# FPGA2.net
KiCad netlist of a schematic drawn in Altium Designer
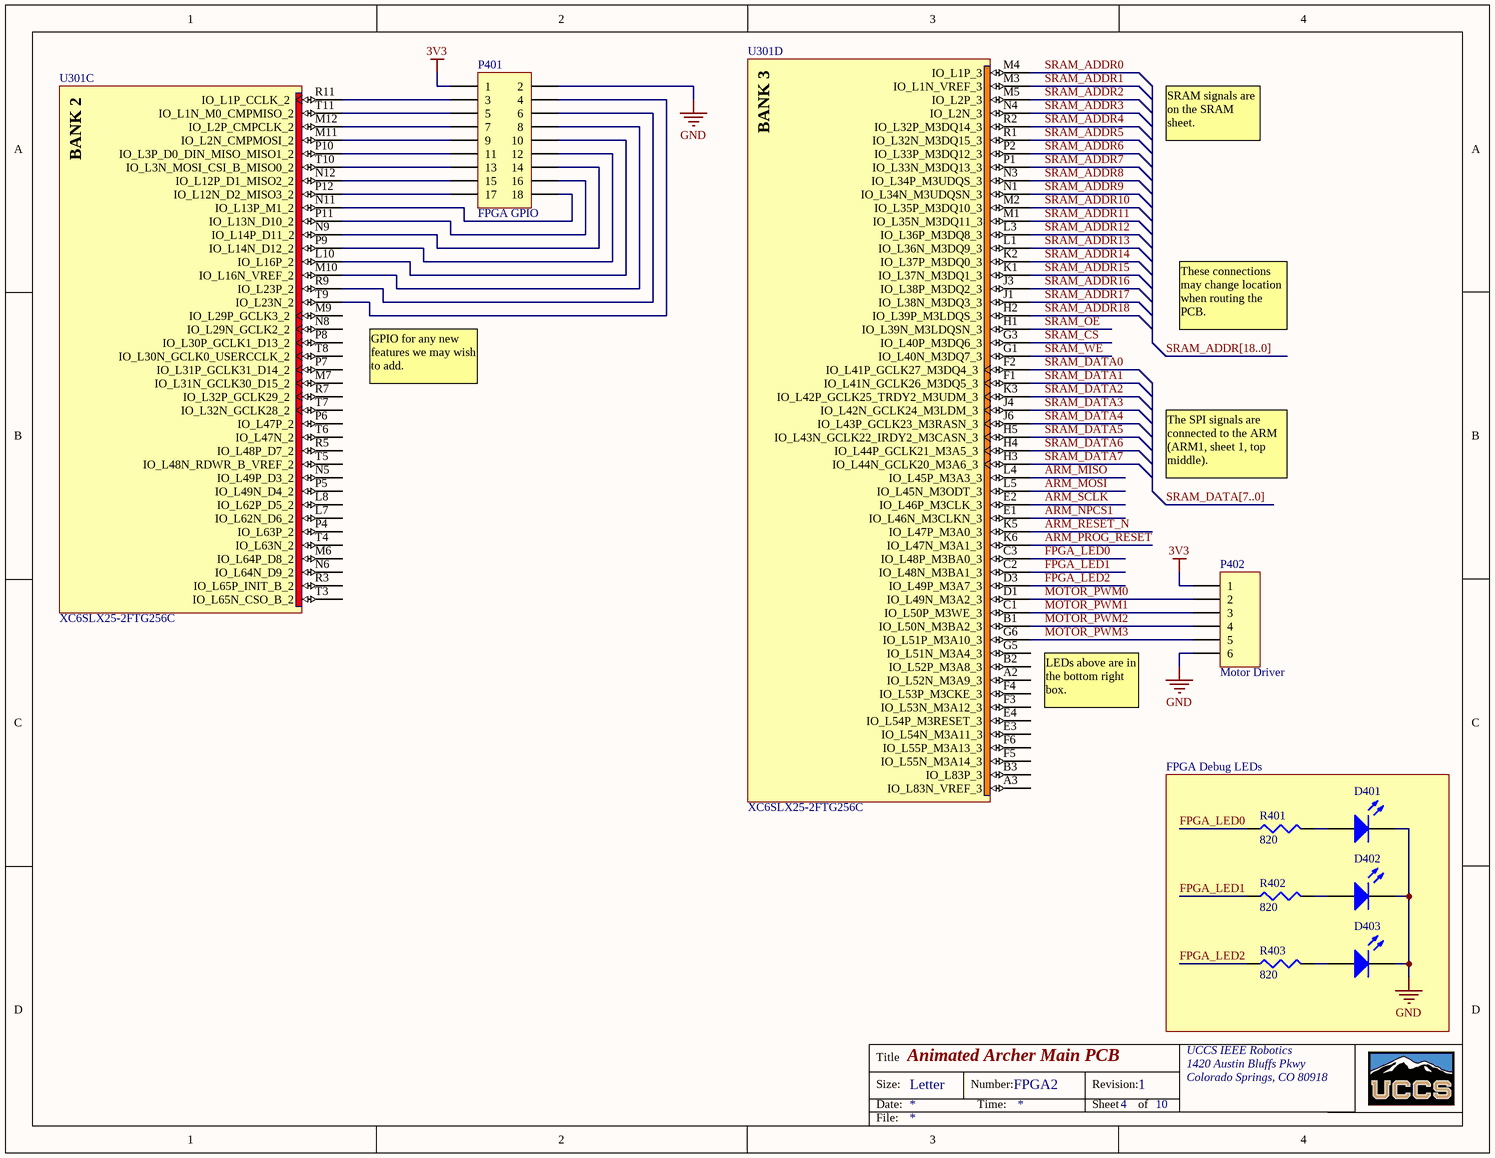
[diagram p0: FPGA2.SchDoc]

(export (version "E")
  (design (tool "Eeschema 10.0.6"))
  (components
    (comp (ref "D401")
      (value "Green")
      (footprint "1608[0603]")
      (description "Typical RED, GREEN, YELLOW, AMBER GaAs LED")
      (fields (field (name "PUBLISHER") "Altium Limited"))
      (libsource (lib "Miscellaneous Devices") (part "LED2"))
    )
    (comp (ref "D402")
      (value "Green")
      (footprint "1608[0603]")
      (description "Typical RED, GREEN, YELLOW, AMBER GaAs LED")
      (fields (field (name "PUBLISHER") "Altium Limited"))
      (libsource (lib "Miscellaneous Devices") (part "LED2"))
    )
    (comp (ref "D403")
      (value "Green")
      (footprint "1608[0603]")
      (description "Typical RED, GREEN, YELLOW, AMBER GaAs LED")
      (fields (field (name "PUBLISHER") "Altium Limited"))
      (libsource (lib "Miscellaneous Devices") (part "LED2"))
    )
    (comp (ref "P401")
      (value "FPGA GPIO")
      (footprint "HDR2X9")
      (description "Header, 9-Pin, Dual row")
      (fields (field (name "PUBLISHER") "Altium Limited"))
      (libsource (lib "Miscellaneous Connectors") (part "Header 9X2"))
    )
    (comp (ref "P402")
      (value "Motor Driver")
      (footprint "HDR1X6")
      (description "Header, 6-Pin")
      (fields (field (name "PUBLISHER") "Altium Limited"))
      (libsource (lib "Miscellaneous Connectors") (part "Header 6"))
    )
    (comp (ref "R401")
      (value "820")
      (footprint "J1-0603")
      (description "Resistor")
      (fields (field (name "Comment") "Res3") (field (name "PUBLISHER") "Altium Limited"))
      (libsource (lib "Miscellaneous Devices") (part "Res3"))
    )
    (comp (ref "R402")
      (value "820")
      (footprint "J1-0603")
      (description "Resistor")
      (fields (field (name "Comment") "Res3") (field (name "PUBLISHER") "Altium Limited"))
      (libsource (lib "Miscellaneous Devices") (part "Res3"))
    )
    (comp (ref "R403")
      (value "820")
      (footprint "J1-0603")
      (description "Resistor")
      (fields (field (name "Comment") "Res3") (field (name "PUBLISHER") "Altium Limited"))
      (libsource (lib "Miscellaneous Devices") (part "Res3"))
    )
    (comp (ref "U301")
      (value "XC6SLX25-2FTG256C")
      (footprint "FTG256")
      (fields (field (name "PUBLISHER") "Altium Limited"))
      (libsource (lib "Animated Archer") (part "XC6SLX25-2FTG256C"))
    )
  )
  (nets
    (net (code "1") (name "/ARM_MISO") (class "Default")
      (node (ref "U301") (pin "L4") (pinfunction "IO_L45P_M3A3_3_L4") (pintype "bidirectional"))
    )
    (net (code "2") (name "/ARM_MOSI") (class "Default")
      (node (ref "U301") (pin "L5") (pinfunction "IO_L45N_M3ODT_3_L5") (pintype "bidirectional"))
    )
    (net (code "3") (name "/ARM_NPCS1") (class "Default")
      (node (ref "U301") (pin "E1") (pinfunction "IO_L46N_M3CLKN_3_E1") (pintype "bidirectional"))
    )
    (net (code "4") (name "/ARM_PROG_RESET") (class "Default")
      (node (ref "U301") (pin "K6") (pinfunction "IO_L47N_M3A1_3_K6") (pintype "bidirectional"))
    )
    (net (code "5") (name "/ARM_RESET_N") (class "Default")
      (node (ref "U301") (pin "K5") (pinfunction "IO_L47P_M3A0_3_K5") (pintype "bidirectional"))
    )
    (net (code "6") (name "/ARM_SCLK") (class "Default")
      (node (ref "U301") (pin "E2") (pinfunction "IO_L46P_M3CLK_3_E2") (pintype "bidirectional"))
    )
    (net (code "7") (name "/FPGA_LED0") (class "Default")
      (node (ref "R401") (pin "1") (pinfunction "1_1") (pintype "passive"))
      (node (ref "U301") (pin "C3") (pinfunction "IO_L48P_M3BA0_3_C3") (pintype "bidirectional"))
    )
    (net (code "8") (name "/FPGA_LED1") (class "Default")
      (node (ref "R402") (pin "1") (pinfunction "1_1") (pintype "passive"))
      (node (ref "U301") (pin "C2") (pinfunction "IO_L48N_M3BA1_3_C2") (pintype "bidirectional"))
    )
    (net (code "9") (name "/FPGA_LED2") (class "Default")
      (node (ref "R403") (pin "1") (pinfunction "1_1") (pintype "passive"))
      (node (ref "U301") (pin "D3") (pinfunction "IO_L49P_M3A7_3_D3") (pintype "bidirectional"))
    )
    (net (code "10") (name "/MOTOR_PWM0") (class "Default")
      (node (ref "P402") (pin "2") (pinfunction "2_2") (pintype "passive"))
      (node (ref "U301") (pin "D1") (pinfunction "IO_L49N_M3A2_3_D1") (pintype "bidirectional"))
    )
    (net (code "11") (name "/MOTOR_PWM1") (class "Default")
      (node (ref "P402") (pin "3") (pinfunction "3_3") (pintype "passive"))
      (node (ref "U301") (pin "C1") (pinfunction "IO_L50P_M3WE_3_C1") (pintype "bidirectional"))
    )
    (net (code "12") (name "/MOTOR_PWM2") (class "Default")
      (node (ref "P402") (pin "4") (pinfunction "4_4") (pintype "passive"))
      (node (ref "U301") (pin "B1") (pinfunction "IO_L50N_M3BA2_3_B1") (pintype "bidirectional"))
    )
    (net (code "13") (name "/MOTOR_PWM3") (class "Default")
      (node (ref "P402") (pin "5") (pinfunction "5_5") (pintype "passive"))
      (node (ref "U301") (pin "G6") (pinfunction "IO_L51P_M3A10_3_G6") (pintype "bidirectional"))
    )
    (net (code "14") (name "/SRAM_ADDR0") (class "Default")
      (node (ref "U301") (pin "M4") (pinfunction "IO_L1P_3_M4") (pintype "bidirectional"))
    )
    (net (code "15") (name "/SRAM_ADDR1") (class "Default")
      (node (ref "U301") (pin "M3") (pinfunction "IO_L1N_VREF_3_M3") (pintype "bidirectional"))
    )
    (net (code "16") (name "/SRAM_ADDR2") (class "Default")
      (node (ref "U301") (pin "M5") (pinfunction "IO_L2P_3_M5") (pintype "bidirectional"))
    )
    (net (code "17") (name "/SRAM_ADDR3") (class "Default")
      (node (ref "U301") (pin "N4") (pinfunction "IO_L2N_3_N4") (pintype "bidirectional"))
    )
    (net (code "18") (name "/SRAM_ADDR4") (class "Default")
      (node (ref "U301") (pin "R2") (pinfunction "IO_L32P_M3DQ14_3_R2") (pintype "bidirectional"))
    )
    (net (code "19") (name "/SRAM_ADDR5") (class "Default")
      (node (ref "U301") (pin "R1") (pinfunction "IO_L32N_M3DQ15_3_R1") (pintype "bidirectional"))
    )
    (net (code "20") (name "/SRAM_ADDR6") (class "Default")
      (node (ref "U301") (pin "P2") (pinfunction "IO_L33P_M3DQ12_3_P2") (pintype "bidirectional"))
    )
    (net (code "21") (name "/SRAM_ADDR7") (class "Default")
      (node (ref "U301") (pin "P1") (pinfunction "IO_L33N_M3DQ13_3_P1") (pintype "bidirectional"))
    )
    (net (code "22") (name "/SRAM_ADDR8") (class "Default")
      (node (ref "U301") (pin "N3") (pinfunction "IO_L34P_M3UDQS_3_N3") (pintype "bidirectional"))
    )
    (net (code "23") (name "/SRAM_ADDR9") (class "Default")
      (node (ref "U301") (pin "N1") (pinfunction "IO_L34N_M3UDQSN_3_N1") (pintype "bidirectional"))
    )
    (net (code "24") (name "/SRAM_ADDR10") (class "Default")
      (node (ref "U301") (pin "M2") (pinfunction "IO_L35P_M3DQ10_3_M2") (pintype "bidirectional"))
    )
    (net (code "25") (name "/SRAM_ADDR11") (class "Default")
      (node (ref "U301") (pin "M1") (pinfunction "IO_L35N_M3DQ11_3_M1") (pintype "bidirectional"))
    )
    (net (code "26") (name "/SRAM_ADDR12") (class "Default")
      (node (ref "U301") (pin "L3") (pinfunction "IO_L36P_M3DQ8_3_L3") (pintype "bidirectional"))
    )
    (net (code "27") (name "/SRAM_ADDR13") (class "Default")
      (node (ref "U301") (pin "L1") (pinfunction "IO_L36N_M3DQ9_3_L1") (pintype "bidirectional"))
    )
    (net (code "28") (name "/SRAM_ADDR14") (class "Default")
      (node (ref "U301") (pin "K2") (pinfunction "IO_L37P_M3DQ0_3_K2") (pintype "bidirectional"))
    )
    (net (code "29") (name "/SRAM_ADDR15") (class "Default")
      (node (ref "U301") (pin "K1") (pinfunction "IO_L37N_M3DQ1_3_K1") (pintype "bidirectional"))
    )
    (net (code "30") (name "/SRAM_ADDR16") (class "Default")
      (node (ref "U301") (pin "J3") (pinfunction "IO_L38P_M3DQ2_3_J3") (pintype "bidirectional"))
    )
    (net (code "31") (name "/SRAM_ADDR17") (class "Default")
      (node (ref "U301") (pin "J1") (pinfunction "IO_L38N_M3DQ3_3_J1") (pintype "bidirectional"))
    )
    (net (code "32") (name "/SRAM_ADDR18") (class "Default")
      (node (ref "U301") (pin "H2") (pinfunction "IO_L39P_M3LDQS_3_H2") (pintype "bidirectional"))
    )
    (net (code "34") (name "/SRAM_CS") (class "Default")
      (node (ref "U301") (pin "G3") (pinfunction "IO_L40P_M3DQ6_3_G3") (pintype "bidirectional"))
    )
    (net (code "35") (name "/SRAM_DATA0") (class "Default")
      (node (ref "U301") (pin "F2") (pinfunction "IO_L41P_GCLK27_M3DQ4_3_F2") (pintype "bidirectional"))
    )
    (net (code "36") (name "/SRAM_DATA1") (class "Default")
      (node (ref "U301") (pin "F1") (pinfunction "IO_L41N_GCLK26_M3DQ5_3_F1") (pintype "bidirectional"))
    )
    (net (code "37") (name "/SRAM_DATA2") (class "Default")
      (node (ref "U301") (pin "K3") (pinfunction "IO_L42P_GCLK25_TRDY2_M3UDM_3_K3") (pintype "bidirectional"))
    )
    (net (code "38") (name "/SRAM_DATA3") (class "Default")
      (node (ref "U301") (pin "J4") (pinfunction "IO_L42N_GCLK24_M3LDM_3_J4") (pintype "bidirectional"))
    )
    (net (code "39") (name "/SRAM_DATA4") (class "Default")
      (node (ref "U301") (pin "J6") (pinfunction "IO_L43P_GCLK23_M3RASN_3_J6") (pintype "bidirectional"))
    )
    (net (code "40") (name "/SRAM_DATA5") (class "Default")
      (node (ref "U301") (pin "H5") (pinfunction "IO_L43N_GCLK22_IRDY2_M3CASN_3_H5") (pintype "bidirectional"))
    )
    (net (code "41") (name "/SRAM_DATA6") (class "Default")
      (node (ref "U301") (pin "H4") (pinfunction "IO_L44P_GCLK21_M3A5_3_H4") (pintype "bidirectional"))
    )
    (net (code "42") (name "/SRAM_DATA7") (class "Default")
      (node (ref "U301") (pin "H3") (pinfunction "IO_L44N_GCLK20_M3A6_3_H3") (pintype "bidirectional"))
    )
    (net (code "44") (name "/SRAM_OE") (class "Default")
      (node (ref "U301") (pin "H1") (pinfunction "IO_L39N_M3LDQSN_3_H1") (pintype "bidirectional"))
    )
    (net (code "45") (name "/SRAM_WE") (class "Default")
      (node (ref "U301") (pin "G1") (pinfunction "IO_L40N_M3DQ7_3_G1") (pintype "bidirectional"))
    )
    (net (code "46") (name "3V3") (class "Default")
      (node (ref "P401") (pin "1") (pinfunction "1_1") (pintype "passive"))
      (node (ref "P402") (pin "1") (pinfunction "1_1") (pintype "passive"))
    )
    (net (code "47") (name "GND") (class "Default")
      (node (ref "D401") (pin "2") (pinfunction "K_2") (pintype "passive"))
      (node (ref "D402") (pin "2") (pinfunction "K_2") (pintype "passive"))
      (node (ref "D403") (pin "2") (pinfunction "K_2") (pintype "passive"))
      (node (ref "P401") (pin "2") (pinfunction "2_2") (pintype "passive"))
      (node (ref "P402") (pin "6") (pinfunction "6_6") (pintype "passive"))
    )
    (net (code "48") (name "Net-(D401-A)") (class "Default")
      (node (ref "D401") (pin "1") (pinfunction "A_1") (pintype "passive"))
      (node (ref "R401") (pin "2") (pinfunction "2_2") (pintype "passive"))
    )
    (net (code "49") (name "Net-(D402-A)") (class "Default")
      (node (ref "D402") (pin "1") (pinfunction "A_1") (pintype "passive"))
      (node (ref "R402") (pin "2") (pinfunction "2_2") (pintype "passive"))
    )
    (net (code "50") (name "Net-(D403-A)") (class "Default")
      (node (ref "D403") (pin "1") (pinfunction "A_1") (pintype "passive"))
      (node (ref "R403") (pin "2") (pinfunction "2_2") (pintype "passive"))
    )
    (net (code "51") (name "Net-(U301C-IO_L1N_M0_CMPMISO_2)") (class "Default")
      (node (ref "P401") (pin "5") (pinfunction "5_5") (pintype "passive"))
      (node (ref "U301") (pin "T11") (pinfunction "IO_L1N_M0_CMPMISO_2_T11") (pintype "bidirectional"))
    )
    (net (code "52") (name "Net-(U301C-IO_L1P_CCLK_2)") (class "Default")
      (node (ref "P401") (pin "3") (pinfunction "3_3") (pintype "passive"))
      (node (ref "U301") (pin "R11") (pinfunction "IO_L1P_CCLK_2_R11") (pintype "bidirectional"))
    )
    (net (code "53") (name "Net-(U301C-IO_L2N_CMPMOSI_2)") (class "Default")
      (node (ref "P401") (pin "9") (pinfunction "9_9") (pintype "passive"))
      (node (ref "U301") (pin "M11") (pinfunction "IO_L2N_CMPMOSI_2_M11") (pintype "bidirectional"))
    )
    (net (code "54") (name "Net-(U301C-IO_L2P_CMPCLK_2)") (class "Default")
      (node (ref "P401") (pin "7") (pinfunction "7_7") (pintype "passive"))
      (node (ref "U301") (pin "M12") (pinfunction "IO_L2P_CMPCLK_2_M12") (pintype "bidirectional"))
    )
    (net (code "55") (name "Net-(U301C-IO_L3N_MOSI_CSI_B_MISO0_2)") (class "Default")
      (node (ref "P401") (pin "13") (pinfunction "13_13") (pintype "passive"))
      (node (ref "U301") (pin "T10") (pinfunction "IO_L3N_MOSI_CSI_B_MISO0_2_T10") (pintype "bidirectional"))
    )
    (net (code "56") (name "Net-(U301C-IO_L3P_D0_DIN_MISO_MISO1_2)") (class "Default")
      (node (ref "P401") (pin "11") (pinfunction "11_11") (pintype "passive"))
      (node (ref "U301") (pin "P10") (pinfunction "IO_L3P_D0_DIN_MISO_MISO1_2_P10") (pintype "bidirectional"))
    )
    (net (code "57") (name "Net-(U301C-IO_L12N_D2_MISO3_2)") (class "Default")
      (node (ref "P401") (pin "17") (pinfunction "17_17") (pintype "passive"))
      (node (ref "U301") (pin "P12") (pinfunction "IO_L12N_D2_MISO3_2_P12") (pintype "bidirectional"))
    )
    (net (code "58") (name "Net-(U301C-IO_L12P_D1_MISO2_2)") (class "Default")
      (node (ref "P401") (pin "15") (pinfunction "15_15") (pintype "passive"))
      (node (ref "U301") (pin "N12") (pinfunction "IO_L12P_D1_MISO2_2_N12") (pintype "bidirectional"))
    )
    (net (code "59") (name "Net-(U301C-IO_L13N_D10_2)") (class "Default")
      (node (ref "P401") (pin "16") (pinfunction "16_16") (pintype "passive"))
      (node (ref "U301") (pin "P11") (pinfunction "IO_L13N_D10_2_P11") (pintype "bidirectional"))
    )
    (net (code "60") (name "Net-(U301C-IO_L13P_M1_2)") (class "Default")
      (node (ref "P401") (pin "18") (pinfunction "18_18") (pintype "passive"))
      (node (ref "U301") (pin "N11") (pinfunction "IO_L13P_M1_2_N11") (pintype "bidirectional"))
    )
    (net (code "61") (name "Net-(U301C-IO_L14N_D12_2)") (class "Default")
      (node (ref "P401") (pin "12") (pinfunction "12_12") (pintype "passive"))
      (node (ref "U301") (pin "P9") (pinfunction "IO_L14N_D12_2_P9") (pintype "bidirectional"))
    )
    (net (code "62") (name "Net-(U301C-IO_L14P_D11_2)") (class "Default")
      (node (ref "P401") (pin "14") (pinfunction "14_14") (pintype "passive"))
      (node (ref "U301") (pin "N9") (pinfunction "IO_L14P_D11_2_N9") (pintype "bidirectional"))
    )
    (net (code "63") (name "Net-(U301C-IO_L16N_VREF_2)") (class "Default")
      (node (ref "P401") (pin "8") (pinfunction "8_8") (pintype "passive"))
      (node (ref "U301") (pin "M10") (pinfunction "IO_L16N_VREF_2_M10") (pintype "bidirectional"))
    )
    (net (code "64") (name "Net-(U301C-IO_L16P_2)") (class "Default")
      (node (ref "P401") (pin "10") (pinfunction "10_10") (pintype "passive"))
      (node (ref "U301") (pin "L10") (pinfunction "IO_L16P_2_L10") (pintype "bidirectional"))
    )
    (net (code "65") (name "Net-(U301C-IO_L23N_2)") (class "Default")
      (node (ref "P401") (pin "4") (pinfunction "4_4") (pintype "passive"))
      (node (ref "U301") (pin "T9") (pinfunction "IO_L23N_2_T9") (pintype "bidirectional"))
    )
    (net (code "66") (name "Net-(U301C-IO_L23P_2)") (class "Default")
      (node (ref "P401") (pin "6") (pinfunction "6_6") (pintype "passive"))
      (node (ref "U301") (pin "R9") (pinfunction "IO_L23P_2_R9") (pintype "bidirectional"))
    )
    (net (code "67") (name "unconnected-(U301C-IO_L29N_GCLK2_2-PadN8)") (class "Default")
      (node (ref "U301") (pin "N8") (pinfunction "IO_L29N_GCLK2_2_N8") (pintype "bidirectional"))
    )
    (net (code "68") (name "unconnected-(U301C-IO_L29P_GCLK3_2-PadM9)") (class "Default")
      (node (ref "U301") (pin "M9") (pinfunction "IO_L29P_GCLK3_2_M9") (pintype "bidirectional"))
    )
    (net (code "69") (name "unconnected-(U301C-IO_L30N_GCLK0_USERCCLK_2-PadT8)") (class "Default")
      (node (ref "U301") (pin "T8") (pinfunction "IO_L30N_GCLK0_USERCCLK_2_T8") (pintype "bidirectional"))
    )
    (net (code "70") (name "unconnected-(U301C-IO_L30P_GCLK1_D13_2-PadP8)") (class "Default")
      (node (ref "U301") (pin "P8") (pinfunction "IO_L30P_GCLK1_D13_2_P8") (pintype "bidirectional"))
    )
    (net (code "71") (name "unconnected-(U301C-IO_L31N_GCLK30_D15_2-PadM7)") (class "Default")
      (node (ref "U301") (pin "M7") (pinfunction "IO_L31N_GCLK30_D15_2_M7") (pintype "bidirectional"))
    )
    (net (code "72") (name "unconnected-(U301C-IO_L31P_GCLK31_D14_2-PadP7)") (class "Default")
      (node (ref "U301") (pin "P7") (pinfunction "IO_L31P_GCLK31_D14_2_P7") (pintype "bidirectional"))
    )
    (net (code "73") (name "unconnected-(U301C-IO_L32N_GCLK28_2-PadT7)") (class "Default")
      (node (ref "U301") (pin "T7") (pinfunction "IO_L32N_GCLK28_2_T7") (pintype "bidirectional"))
    )
    (net (code "74") (name "unconnected-(U301C-IO_L32P_GCLK29_2-PadR7)") (class "Default")
      (node (ref "U301") (pin "R7") (pinfunction "IO_L32P_GCLK29_2_R7") (pintype "bidirectional"))
    )
    (net (code "75") (name "unconnected-(U301C-IO_L47N_2-PadT6)") (class "Default")
      (node (ref "U301") (pin "T6") (pinfunction "IO_L47N_2_T6") (pintype "bidirectional"))
    )
    (net (code "76") (name "unconnected-(U301C-IO_L47P_2-PadP6)") (class "Default")
      (node (ref "U301") (pin "P6") (pinfunction "IO_L47P_2_P6") (pintype "bidirectional"))
    )
    (net (code "77") (name "unconnected-(U301C-IO_L48N_RDWR_B_VREF_2-PadT5)") (class "Default")
      (node (ref "U301") (pin "T5") (pinfunction "IO_L48N_RDWR_B_VREF_2_T5") (pintype "bidirectional"))
    )
    (net (code "78") (name "unconnected-(U301C-IO_L48P_D7_2-PadR5)") (class "Default")
      (node (ref "U301") (pin "R5") (pinfunction "IO_L48P_D7_2_R5") (pintype "bidirectional"))
    )
    (net (code "79") (name "unconnected-(U301C-IO_L49N_D4_2-PadP5)") (class "Default")
      (node (ref "U301") (pin "P5") (pinfunction "IO_L49N_D4_2_P5") (pintype "bidirectional"))
    )
    (net (code "80") (name "unconnected-(U301C-IO_L49P_D3_2-PadN5)") (class "Default")
      (node (ref "U301") (pin "N5") (pinfunction "IO_L49P_D3_2_N5") (pintype "bidirectional"))
    )
    (net (code "81") (name "unconnected-(U301C-IO_L62N_D6_2-PadL7)") (class "Default")
      (node (ref "U301") (pin "L7") (pinfunction "IO_L62N_D6_2_L7") (pintype "bidirectional"))
    )
    (net (code "82") (name "unconnected-(U301C-IO_L62P_D5_2-PadL8)") (class "Default")
      (node (ref "U301") (pin "L8") (pinfunction "IO_L62P_D5_2_L8") (pintype "bidirectional"))
    )
    (net (code "83") (name "unconnected-(U301C-IO_L63N_2-PadT4)") (class "Default")
      (node (ref "U301") (pin "T4") (pinfunction "IO_L63N_2_T4") (pintype "bidirectional"))
    )
    (net (code "84") (name "unconnected-(U301C-IO_L63P_2-PadP4)") (class "Default")
      (node (ref "U301") (pin "P4") (pinfunction "IO_L63P_2_P4") (pintype "bidirectional"))
    )
    (net (code "85") (name "unconnected-(U301C-IO_L64N_D9_2-PadN6)") (class "Default")
      (node (ref "U301") (pin "N6") (pinfunction "IO_L64N_D9_2_N6") (pintype "bidirectional"))
    )
    (net (code "86") (name "unconnected-(U301C-IO_L64P_D8_2-PadM6)") (class "Default")
      (node (ref "U301") (pin "M6") (pinfunction "IO_L64P_D8_2_M6") (pintype "bidirectional"))
    )
    (net (code "87") (name "unconnected-(U301C-IO_L65N_CSO_B_2-PadT3)") (class "Default")
      (node (ref "U301") (pin "T3") (pinfunction "IO_L65N_CSO_B_2_T3") (pintype "bidirectional"))
    )
    (net (code "88") (name "unconnected-(U301C-IO_L65P_INIT_B_2-PadR3)") (class "Default")
      (node (ref "U301") (pin "R3") (pinfunction "IO_L65P_INIT_B_2_R3") (pintype "bidirectional"))
    )
    (net (code "89") (name "unconnected-(U301D-IO_L51N_M3A4_3-PadG5)") (class "Default")
      (node (ref "U301") (pin "G5") (pinfunction "IO_L51N_M3A4_3_G5") (pintype "bidirectional"))
    )
    (net (code "90") (name "unconnected-(U301D-IO_L52N_M3A9_3-PadA2)") (class "Default")
      (node (ref "U301") (pin "A2") (pinfunction "IO_L52N_M3A9_3_A2") (pintype "bidirectional"))
    )
    (net (code "91") (name "unconnected-(U301D-IO_L52P_M3A8_3-PadB2)") (class "Default")
      (node (ref "U301") (pin "B2") (pinfunction "IO_L52P_M3A8_3_B2") (pintype "bidirectional"))
    )
    (net (code "92") (name "unconnected-(U301D-IO_L53N_M3A12_3-PadF3)") (class "Default")
      (node (ref "U301") (pin "F3") (pinfunction "IO_L53N_M3A12_3_F3") (pintype "bidirectional"))
    )
    (net (code "93") (name "unconnected-(U301D-IO_L53P_M3CKE_3-PadF4)") (class "Default")
      (node (ref "U301") (pin "F4") (pinfunction "IO_L53P_M3CKE_3_F4") (pintype "bidirectional"))
    )
    (net (code "94") (name "unconnected-(U301D-IO_L54N_M3A11_3-PadE3)") (class "Default")
      (node (ref "U301") (pin "E3") (pinfunction "IO_L54N_M3A11_3_E3") (pintype "bidirectional"))
    )
    (net (code "95") (name "unconnected-(U301D-IO_L54P_M3RESET_3-PadE4)") (class "Default")
      (node (ref "U301") (pin "E4") (pinfunction "IO_L54P_M3RESET_3_E4") (pintype "bidirectional"))
    )
    (net (code "96") (name "unconnected-(U301D-IO_L55N_M3A14_3-PadF5)") (class "Default")
      (node (ref "U301") (pin "F5") (pinfunction "IO_L55N_M3A14_3_F5") (pintype "bidirectional"))
    )
    (net (code "97") (name "unconnected-(U301D-IO_L55P_M3A13_3-PadF6)") (class "Default")
      (node (ref "U301") (pin "F6") (pinfunction "IO_L55P_M3A13_3_F6") (pintype "bidirectional"))
    )
    (net (code "98") (name "unconnected-(U301D-IO_L83N_VREF_3-PadA3)") (class "Default")
      (node (ref "U301") (pin "A3") (pinfunction "IO_L83N_VREF_3_A3") (pintype "bidirectional"))
    )
    (net (code "99") (name "unconnected-(U301D-IO_L83P_3-PadB3)") (class "Default")
      (node (ref "U301") (pin "B3") (pinfunction "IO_L83P_3_B3") (pintype "bidirectional"))
    )
  )
)
